# utility_hat.net
KiCad netlist of a schematic drawn in EAGLE
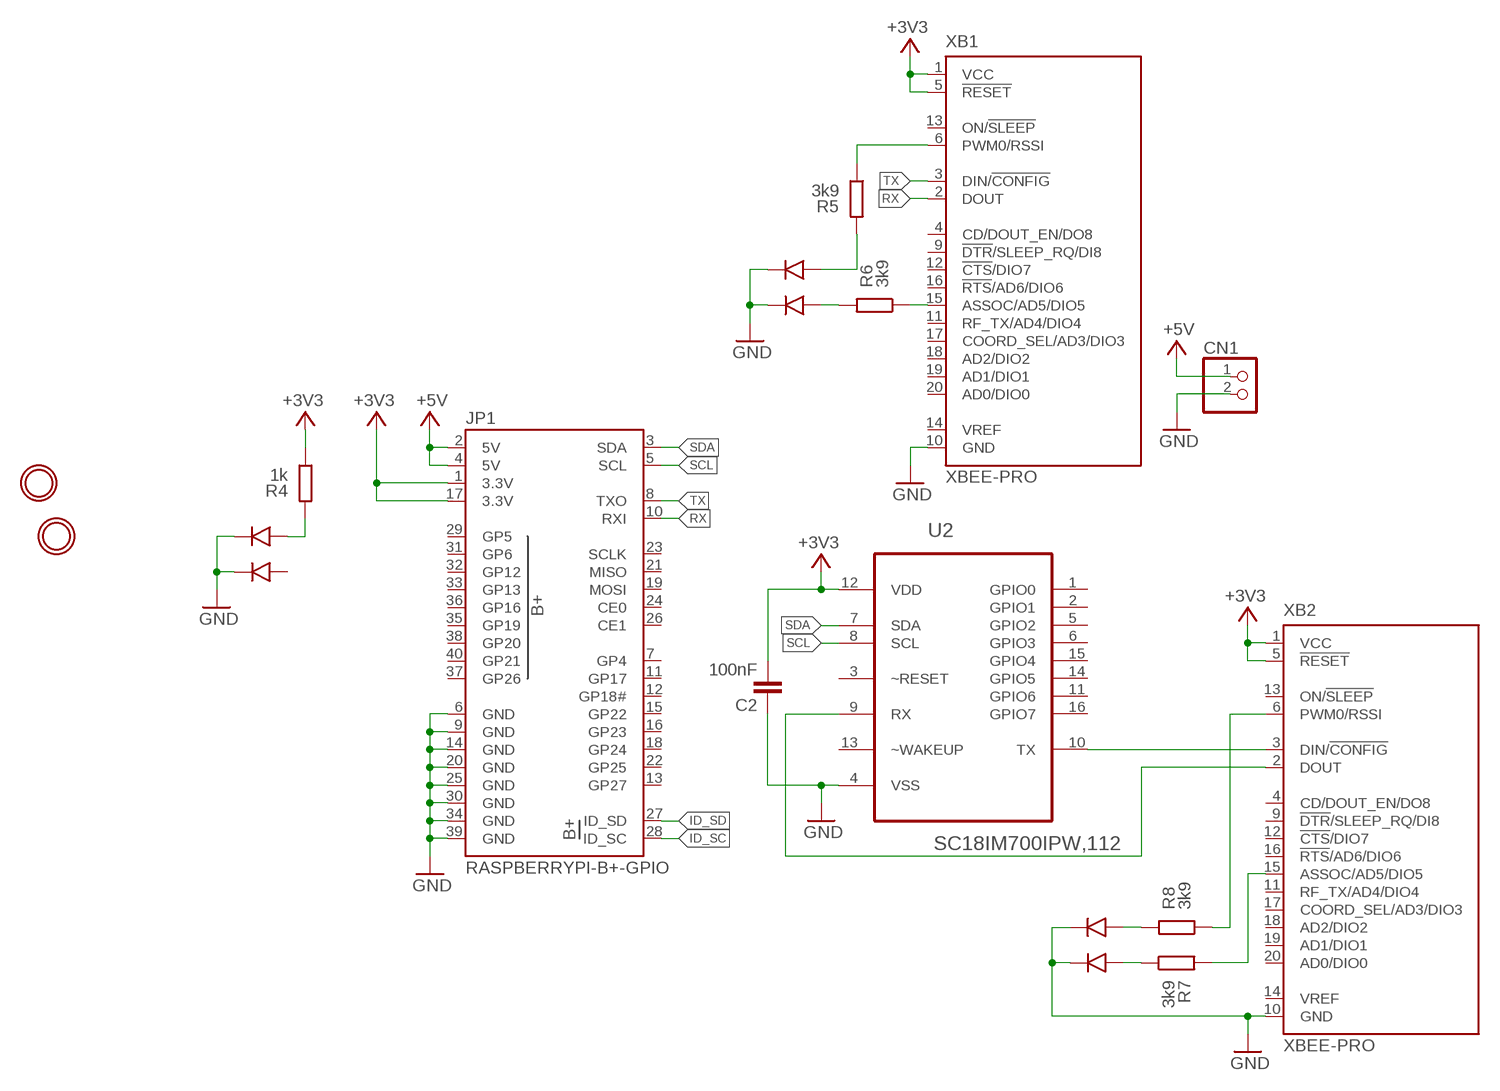
[diagram p0: schematic, sheet 1]

(export (version "E")
  (design (tool "Eeschema 10.0.6"))
  (components
    (comp (ref "C2")
      (value "100nF")
      (footprint "eagle-import:C0805K")
      (libsource (lib "eagle-import") (part "C-EUC0805K"))
    )
    (comp (ref "CN1")
      (value "JST_2PIN")
      (footprint "eagle-import:JSTPH2")
      (libsource (lib "eagle-import") (part "JST_2PIN"))
    )
    (comp (ref "JP1")
      (value "RASPBERRYPI-B+-GPIO")
      (footprint "eagle-import:2X20-SHROUDED")
      (libsource (lib "eagle-import") (part "RASPBERRYPI-B+-GPIO"))
    )
    (comp (ref "R4")
      (value "1k")
      (footprint "eagle-import:M0805")
      (fields (field (name "TOLERANCE") "5%"))
      (libsource (lib "eagle-import") (part "R-EU_M0805"))
    )
    (comp (ref "R5")
      (value "3k9")
      (footprint "eagle-import:M0805")
      (fields (field (name "TOLERANCE") "5%"))
      (libsource (lib "eagle-import") (part "R-EU_M0805"))
    )
    (comp (ref "R6")
      (value "3k9")
      (footprint "eagle-import:M0805")
      (fields (field (name "TOLERANCE") "5%"))
      (libsource (lib "eagle-import") (part "R-EU_M0805"))
    )
    (comp (ref "R7")
      (value "3k9")
      (footprint "eagle-import:M0805")
      (fields (field (name "TOLERANCE") "5%"))
      (libsource (lib "eagle-import") (part "R-EU_M0805"))
    )
    (comp (ref "R8")
      (value "3k9")
      (footprint "eagle-import:M0805")
      (fields (field (name "TOLERANCE") "5%"))
      (libsource (lib "eagle-import") (part "R-EU_M0805"))
    )
    (comp (ref "U$1")
      (value "BI-LEVEL-LED-INDICATOR")
      (footprint "eagle-import:BI-LEVEL-LED-INDICATOR")
      (libsource (lib "eagle-import") (part "BI-LEVEL-LED-INDICATOR"))
    )
    (comp (ref "U$2")
      (value "BI-LEVEL-LED-INDICATOR")
      (footprint "eagle-import:BI-LEVEL-LED-INDICATOR")
      (libsource (lib "eagle-import") (part "BI-LEVEL-LED-INDICATOR"))
    )
    (comp (ref "U$3")
      (value "BI-LEVEL-LED-INDICATOR")
      (footprint "eagle-import:BI-LEVEL-LED-INDICATOR")
      (libsource (lib "eagle-import") (part "BI-LEVEL-LED-INDICATOR"))
    )
    (comp (ref "U$4")
      (value "MOUNTINGHOLE3.0THIN")
      (footprint "eagle-import:MOUNTINGHOLE_3.0_PLATEDTHIN")
      (libsource (lib "eagle-import") (part "MOUNTINGHOLE3.0THIN"))
    )
    (comp (ref "U$5")
      (value "MOUNTINGHOLE3.0THIN")
      (footprint "eagle-import:MOUNTINGHOLE_3.0_PLATEDTHIN")
      (libsource (lib "eagle-import") (part "MOUNTINGHOLE3.0THIN"))
    )
    (comp (ref "U2")
      (value "SC18IM700IPW,112")
      (footprint "eagle-import:SOP65P640X110-16N")
      (libsource (lib "eagle-import") (part "SC18IM700IPW,112"))
    )
    (comp (ref "XB1")
      (value "XBEE-PRO")
      (footprint "eagle-import:XBEE-PRO")
      (fields (field (name "MPN") "XBP24-AWI-001"))
      (libsource (lib "eagle-import") (part "XBEE-PRO"))
    )
    (comp (ref "XB2")
      (value "XBEE-PRO")
      (footprint "eagle-import:XBEE-PRO")
      (fields
        (field (name "MPN") "XBP24-AWI-001")
        (field (name "MPN_1") "XBP24-AWI-001")
        (field (name "OC_FARNELL") "1337916")
        (field (name "OC_NEWARK") "42M2667")
      )
      (libsource (lib "eagle-import") (part "XBEE-PRO"))
    )
  )
  (nets
    (net (code "1") (name "+3V3") (class "Default")
      (node (ref "C2") (pin "2") (pinfunction "2_2") (pintype "passive"))
      (node (ref "JP1") (pin "1") (pinfunction "3.3V_1") (pintype "power_in"))
      (node (ref "JP1") (pin "17") (pinfunction "3.3V_17") (pintype "power_in"))
      (node (ref "R4") (pin "1") (pinfunction "1_1") (pintype "passive"))
      (node (ref "U2") (pin "12") (pinfunction "VDD_12") (pintype "power_in"))
      (node (ref "XB1") (pin "1") (pinfunction "VCC_1") (pintype "power_in"))
      (node (ref "XB1") (pin "5") (pinfunction "~{RESET}_5") (pintype "input"))
      (node (ref "XB2") (pin "1") (pinfunction "VCC_1") (pintype "power_in"))
      (node (ref "XB2") (pin "5") (pinfunction "~{RESET}_5") (pintype "input"))
    )
    (net (code "2") (name "+5V") (class "Default")
      (node (ref "CN1") (pin "1") (pinfunction "1_1") (pintype "passive"))
      (node (ref "JP1") (pin "2") (pinfunction "5V_2") (pintype "power_in"))
      (node (ref "JP1") (pin "4") (pinfunction "5V_4") (pintype "power_in"))
    )
    (net (code "3") (name "GND") (class "Default")
      (node (ref "C2") (pin "1") (pinfunction "1_1") (pintype "passive"))
      (node (ref "CN1") (pin "2") (pinfunction "2_2") (pintype "passive"))
      (node (ref "JP1") (pin "14") (pinfunction "GND_14") (pintype "power_in"))
      (node (ref "JP1") (pin "20") (pinfunction "GND_20") (pintype "power_in"))
      (node (ref "JP1") (pin "25") (pinfunction "GND_25") (pintype "power_in"))
      (node (ref "JP1") (pin "30") (pinfunction "GND_30") (pintype "power_in"))
      (node (ref "JP1") (pin "34") (pinfunction "GND_34") (pintype "power_in"))
      (node (ref "JP1") (pin "39") (pinfunction "GND_39") (pintype "power_in"))
      (node (ref "JP1") (pin "6") (pinfunction "GND_6") (pintype "power_in"))
      (node (ref "JP1") (pin "9") (pinfunction "GND_9") (pintype "power_in"))
      (node (ref "U$1") (pin "CATHODE1") (pinfunction "CATHODE1_CATHODE1") (pintype "bidirectional"))
      (node (ref "U$1") (pin "CATHODE2") (pinfunction "CATHODE2_CATHODE2") (pintype "bidirectional"))
      (node (ref "U$2") (pin "CATHODE1") (pinfunction "CATHODE1_CATHODE1") (pintype "bidirectional"))
      (node (ref "U$2") (pin "CATHODE2") (pinfunction "CATHODE2_CATHODE2") (pintype "bidirectional"))
      (node (ref "U$3") (pin "CATHODE1") (pinfunction "CATHODE1_CATHODE1") (pintype "bidirectional"))
      (node (ref "U$3") (pin "CATHODE2") (pinfunction "CATHODE2_CATHODE2") (pintype "bidirectional"))
      (node (ref "U2") (pin "4") (pinfunction "VSS_4") (pintype "passive"))
      (node (ref "XB1") (pin "10") (pinfunction "GND_10") (pintype "power_in"))
      (node (ref "XB2") (pin "10") (pinfunction "GND_10") (pintype "power_in"))
    )
    (net (code "4") (name "ID_SC") (class "Default")
      (node (ref "JP1") (pin "28") (pinfunction "ID_SC_28") (pintype "bidirectional"))
    )
    (net (code "5") (name "ID_SD") (class "Default")
      (node (ref "JP1") (pin "27") (pinfunction "ID_SD_27") (pintype "bidirectional"))
    )
    (net (code "6") (name "Net-(R4-Pad2)") (class "Default")
      (node (ref "R4") (pin "2") (pinfunction "2_2") (pintype "passive"))
      (node (ref "U$3") (pin "ANODE1") (pinfunction "ANODE1_ANODE1") (pintype "bidirectional"))
    )
    (net (code "7") (name "Net-(R5-Pad2)") (class "Default")
      (node (ref "R5") (pin "2") (pinfunction "2_2") (pintype "passive"))
      (node (ref "U$1") (pin "ANODE1") (pinfunction "ANODE1_ANODE1") (pintype "bidirectional"))
    )
    (net (code "8") (name "Net-(R6-Pad2)") (class "Default")
      (node (ref "R6") (pin "2") (pinfunction "2_2") (pintype "passive"))
      (node (ref "U$1") (pin "ANODE2") (pinfunction "ANODE2_ANODE2") (pintype "bidirectional"))
    )
    (net (code "9") (name "Net-(R7-Pad1)") (class "Default")
      (node (ref "R7") (pin "1") (pinfunction "1_1") (pintype "passive"))
      (node (ref "U$2") (pin "ANODE2") (pinfunction "ANODE2_ANODE2") (pintype "bidirectional"))
    )
    (net (code "10") (name "Net-(R8-Pad2)") (class "Default")
      (node (ref "R8") (pin "2") (pinfunction "2_2") (pintype "passive"))
      (node (ref "U$2") (pin "ANODE1") (pinfunction "ANODE1_ANODE1") (pintype "bidirectional"))
    )
    (net (code "11") (name "Net-(U2-RX)") (class "Default")
      (node (ref "U2") (pin "9") (pinfunction "RX_9") (pintype "input"))
      (node (ref "XB2") (pin "2") (pinfunction "DOUT_2") (pintype "output"))
    )
    (net (code "12") (name "Net-(U2-TX)") (class "Default")
      (node (ref "U2") (pin "10") (pinfunction "TX_10") (pintype "output"))
      (node (ref "XB2") (pin "3") (pinfunction "DIN/~{CONFIG}_3") (pintype "input"))
    )
    (net (code "13") (name "Net-(XB1-ASSOC{slash}AD5{slash}DIO5)") (class "Default")
      (node (ref "R6") (pin "1") (pinfunction "1_1") (pintype "passive"))
      (node (ref "XB1") (pin "15") (pinfunction "ASSOC/AD5/DIO5_15") (pintype "bidirectional"))
    )
    (net (code "14") (name "Net-(XB1-PWM0{slash}RSSI)") (class "Default")
      (node (ref "R5") (pin "1") (pinfunction "1_1") (pintype "passive"))
      (node (ref "XB1") (pin "6") (pinfunction "PWM0/RSSI_6") (pintype "output"))
    )
    (net (code "15") (name "Net-(XB2-ASSOC{slash}AD5{slash}DIO5)") (class "Default")
      (node (ref "R7") (pin "2") (pinfunction "2_2") (pintype "passive"))
      (node (ref "XB2") (pin "15") (pinfunction "ASSOC/AD5/DIO5_15") (pintype "bidirectional"))
    )
    (net (code "16") (name "Net-(XB2-PWM0{slash}RSSI)") (class "Default")
      (node (ref "R8") (pin "1") (pinfunction "1_1") (pintype "passive"))
      (node (ref "XB2") (pin "6") (pinfunction "PWM0/RSSI_6") (pintype "output"))
    )
    (net (code "17") (name "RX") (class "Default")
      (node (ref "JP1") (pin "10") (pinfunction "RXI_10") (pintype "input"))
      (node (ref "XB1") (pin "2") (pinfunction "DOUT_2") (pintype "output"))
    )
    (net (code "18") (name "SCL") (class "Default")
      (node (ref "JP1") (pin "5") (pinfunction "SCL_5") (pintype "bidirectional"))
      (node (ref "U2") (pin "8") (pinfunction "SCL_8") (pintype "input"))
    )
    (net (code "19") (name "SDA") (class "Default")
      (node (ref "JP1") (pin "3") (pinfunction "SDA_3") (pintype "bidirectional"))
      (node (ref "U2") (pin "7") (pinfunction "SDA_7") (pintype "bidirectional"))
    )
    (net (code "20") (name "TX") (class "Default")
      (node (ref "JP1") (pin "8") (pinfunction "TXO_8") (pintype "output"))
      (node (ref "XB1") (pin "3") (pinfunction "DIN/~{CONFIG}_3") (pintype "input"))
    )
    (net (code "21") (name "unconnected-(JP1-CE0-Pad24)") (class "Default")
      (node (ref "JP1") (pin "24") (pinfunction "CE0_24") (pintype "output"))
    )
    (net (code "22") (name "unconnected-(JP1-CE1-Pad26)") (class "Default")
      (node (ref "JP1") (pin "26") (pinfunction "CE1_26") (pintype "output"))
    )
    (net (code "23") (name "unconnected-(JP1-GP4-Pad7)") (class "Default")
      (node (ref "JP1") (pin "7") (pinfunction "GP4_7") (pintype "bidirectional"))
    )
    (net (code "24") (name "unconnected-(JP1-GP5-Pad29)") (class "Default")
      (node (ref "JP1") (pin "29") (pinfunction "GP5_29") (pintype "bidirectional"))
    )
    (net (code "25") (name "unconnected-(JP1-GP6-Pad31)") (class "Default")
      (node (ref "JP1") (pin "31") (pinfunction "GP6_31") (pintype "bidirectional"))
    )
    (net (code "26") (name "unconnected-(JP1-GP12-Pad32)") (class "Default")
      (node (ref "JP1") (pin "32") (pinfunction "GP12_32") (pintype "bidirectional"))
    )
    (net (code "27") (name "unconnected-(JP1-GP13-Pad33)") (class "Default")
      (node (ref "JP1") (pin "33") (pinfunction "GP13_33") (pintype "bidirectional"))
    )
    (net (code "28") (name "unconnected-(JP1-GP16-Pad36)") (class "Default")
      (node (ref "JP1") (pin "36") (pinfunction "GP16_36") (pintype "bidirectional"))
    )
    (net (code "29") (name "unconnected-(JP1-GP17-Pad11)") (class "Default")
      (node (ref "JP1") (pin "11") (pinfunction "GP17_11") (pintype "bidirectional"))
    )
    (net (code "30") (name "unconnected-(JP1-GP18#-Pad12)") (class "Default")
      (node (ref "JP1") (pin "12") (pinfunction "GP18#_12") (pintype "bidirectional"))
    )
    (net (code "31") (name "unconnected-(JP1-GP19-Pad35)") (class "Default")
      (node (ref "JP1") (pin "35") (pinfunction "GP19_35") (pintype "bidirectional"))
    )
    (net (code "32") (name "unconnected-(JP1-GP20-Pad38)") (class "Default")
      (node (ref "JP1") (pin "38") (pinfunction "GP20_38") (pintype "bidirectional"))
    )
    (net (code "33") (name "unconnected-(JP1-GP21-Pad40)") (class "Default")
      (node (ref "JP1") (pin "40") (pinfunction "GP21_40") (pintype "bidirectional"))
    )
    (net (code "34") (name "unconnected-(JP1-GP22-Pad15)") (class "Default")
      (node (ref "JP1") (pin "15") (pinfunction "GP22_15") (pintype "bidirectional"))
    )
    (net (code "35") (name "unconnected-(JP1-GP23-Pad16)") (class "Default")
      (node (ref "JP1") (pin "16") (pinfunction "GP23_16") (pintype "bidirectional"))
    )
    (net (code "36") (name "unconnected-(JP1-GP24-Pad18)") (class "Default")
      (node (ref "JP1") (pin "18") (pinfunction "GP24_18") (pintype "bidirectional"))
    )
    (net (code "37") (name "unconnected-(JP1-GP25-Pad22)") (class "Default")
      (node (ref "JP1") (pin "22") (pinfunction "GP25_22") (pintype "bidirectional"))
    )
    (net (code "38") (name "unconnected-(JP1-GP26-Pad37)") (class "Default")
      (node (ref "JP1") (pin "37") (pinfunction "GP26_37") (pintype "bidirectional"))
    )
    (net (code "39") (name "unconnected-(JP1-GP27-Pad13)") (class "Default")
      (node (ref "JP1") (pin "13") (pinfunction "GP27_13") (pintype "bidirectional"))
    )
    (net (code "40") (name "unconnected-(JP1-MISO-Pad21)") (class "Default")
      (node (ref "JP1") (pin "21") (pinfunction "MISO_21") (pintype "input"))
    )
    (net (code "41") (name "unconnected-(JP1-MOSI-Pad19)") (class "Default")
      (node (ref "JP1") (pin "19") (pinfunction "MOSI_19") (pintype "output"))
    )
    (net (code "42") (name "unconnected-(JP1-SCLK-Pad23)") (class "Default")
      (node (ref "JP1") (pin "23") (pinfunction "SCLK_23") (pintype "output"))
    )
    (net (code "43") (name "unconnected-(U$3-PadANODE2)") (class "Default")
      (node (ref "U$3") (pin "ANODE2") (pinfunction "ANODE2_ANODE2") (pintype "bidirectional"))
    )
    (net (code "44") (name "unconnected-(U2-GPIO0-Pad1)") (class "Default")
      (node (ref "U2") (pin "1") (pinfunction "GPIO0_1") (pintype "bidirectional"))
    )
    (net (code "45") (name "unconnected-(U2-GPIO1-Pad2)") (class "Default")
      (node (ref "U2") (pin "2") (pinfunction "GPIO1_2") (pintype "bidirectional"))
    )
    (net (code "46") (name "unconnected-(U2-GPIO2-Pad5)") (class "Default")
      (node (ref "U2") (pin "5") (pinfunction "GPIO2_5") (pintype "bidirectional"))
    )
    (net (code "47") (name "unconnected-(U2-GPIO3-Pad6)") (class "Default")
      (node (ref "U2") (pin "6") (pinfunction "GPIO3_6") (pintype "bidirectional"))
    )
    (net (code "48") (name "unconnected-(U2-GPIO4-Pad15)") (class "Default")
      (node (ref "U2") (pin "15") (pinfunction "GPIO4_15") (pintype "bidirectional"))
    )
    (net (code "49") (name "unconnected-(U2-GPIO5-Pad14)") (class "Default")
      (node (ref "U2") (pin "14") (pinfunction "GPIO5_14") (pintype "bidirectional"))
    )
    (net (code "50") (name "unconnected-(U2-GPIO6-Pad11)") (class "Default")
      (node (ref "U2") (pin "11") (pinfunction "GPIO6_11") (pintype "bidirectional"))
    )
    (net (code "51") (name "unconnected-(U2-GPIO7-Pad16)") (class "Default")
      (node (ref "U2") (pin "16") (pinfunction "GPIO7_16") (pintype "bidirectional"))
    )
    (net (code "52") (name "unconnected-(U2-~{RESET}-Pad3)") (class "Default")
      (node (ref "U2") (pin "3") (pinfunction "~{RESET}_3") (pintype "input"))
    )
    (net (code "53") (name "unconnected-(U2-~{WAKEUP}-Pad13)") (class "Default")
      (node (ref "U2") (pin "13") (pinfunction "~{WAKEUP}_13") (pintype "input"))
    )
    (net (code "54") (name "unconnected-(XB1-AD0{slash}DIO0-Pad20)") (class "Default")
      (node (ref "XB1") (pin "20") (pinfunction "AD0/DIO0_20") (pintype "bidirectional"))
    )
    (net (code "55") (name "unconnected-(XB1-AD1{slash}DIO1-Pad19)") (class "Default")
      (node (ref "XB1") (pin "19") (pinfunction "AD1/DIO1_19") (pintype "bidirectional"))
    )
    (net (code "56") (name "unconnected-(XB1-AD2{slash}DIO2-Pad18)") (class "Default")
      (node (ref "XB1") (pin "18") (pinfunction "AD2/DIO2_18") (pintype "bidirectional"))
    )
    (net (code "57") (name "unconnected-(XB1-CD{slash}DOUT_EN{slash}DO8-Pad4)") (class "Default")
      (node (ref "XB1") (pin "4") (pinfunction "CD/DOUT_EN/DO8_4") (pintype "output"))
    )
    (net (code "58") (name "unconnected-(XB1-COORD_SEL{slash}AD3{slash}DIO3-Pad17)") (class "Default")
      (node (ref "XB1") (pin "17") (pinfunction "COORD_SEL/AD3/DIO3_17") (pintype "bidirectional"))
    )
    (net (code "59") (name "unconnected-(XB1-ON{slash}~{SLEEP}-Pad13)") (class "Default")
      (node (ref "XB1") (pin "13") (pinfunction "ON/~{SLEEP}_13") (pintype "output"))
    )
    (net (code "60") (name "unconnected-(XB1-RF_TX{slash}AD4{slash}DIO4-Pad11)") (class "Default")
      (node (ref "XB1") (pin "11") (pinfunction "RF_TX/AD4/DIO4_11") (pintype "bidirectional"))
    )
    (net (code "61") (name "unconnected-(XB1-VREF-Pad14)") (class "Default")
      (node (ref "XB1") (pin "14") (pinfunction "VREF_14") (pintype "input"))
    )
    (net (code "62") (name "unconnected-(XB1-~{CTS}{slash}DIO7-Pad12)") (class "Default")
      (node (ref "XB1") (pin "12") (pinfunction "~{CTS}/DIO7_12") (pintype "bidirectional"))
    )
    (net (code "63") (name "unconnected-(XB1-~{DTR}{slash}SLEEP_RQ{slash}DI8-Pad9)") (class "Default")
      (node (ref "XB1") (pin "9") (pinfunction "~{DTR}/SLEEP_RQ/DI8_9") (pintype "bidirectional"))
    )
    (net (code "64") (name "unconnected-(XB1-~{RTS}{slash}AD6{slash}DIO6-Pad16)") (class "Default")
      (node (ref "XB1") (pin "16") (pinfunction "~{RTS}/AD6/DIO6_16") (pintype "bidirectional"))
    )
    (net (code "65") (name "unconnected-(XB2-AD0{slash}DIO0-Pad20)") (class "Default")
      (node (ref "XB2") (pin "20") (pinfunction "AD0/DIO0_20") (pintype "bidirectional"))
    )
    (net (code "66") (name "unconnected-(XB2-AD1{slash}DIO1-Pad19)") (class "Default")
      (node (ref "XB2") (pin "19") (pinfunction "AD1/DIO1_19") (pintype "bidirectional"))
    )
    (net (code "67") (name "unconnected-(XB2-AD2{slash}DIO2-Pad18)") (class "Default")
      (node (ref "XB2") (pin "18") (pinfunction "AD2/DIO2_18") (pintype "bidirectional"))
    )
    (net (code "68") (name "unconnected-(XB2-CD{slash}DOUT_EN{slash}DO8-Pad4)") (class "Default")
      (node (ref "XB2") (pin "4") (pinfunction "CD/DOUT_EN/DO8_4") (pintype "output"))
    )
    (net (code "69") (name "unconnected-(XB2-COORD_SEL{slash}AD3{slash}DIO3-Pad17)") (class "Default")
      (node (ref "XB2") (pin "17") (pinfunction "COORD_SEL/AD3/DIO3_17") (pintype "bidirectional"))
    )
    (net (code "70") (name "unconnected-(XB2-ON{slash}~{SLEEP}-Pad13)") (class "Default")
      (node (ref "XB2") (pin "13") (pinfunction "ON/~{SLEEP}_13") (pintype "output"))
    )
    (net (code "71") (name "unconnected-(XB2-RF_TX{slash}AD4{slash}DIO4-Pad11)") (class "Default")
      (node (ref "XB2") (pin "11") (pinfunction "RF_TX/AD4/DIO4_11") (pintype "bidirectional"))
    )
    (net (code "72") (name "unconnected-(XB2-VREF-Pad14)") (class "Default")
      (node (ref "XB2") (pin "14") (pinfunction "VREF_14") (pintype "input"))
    )
    (net (code "73") (name "unconnected-(XB2-~{CTS}{slash}DIO7-Pad12)") (class "Default")
      (node (ref "XB2") (pin "12") (pinfunction "~{CTS}/DIO7_12") (pintype "bidirectional"))
    )
    (net (code "74") (name "unconnected-(XB2-~{DTR}{slash}SLEEP_RQ{slash}DI8-Pad9)") (class "Default")
      (node (ref "XB2") (pin "9") (pinfunction "~{DTR}/SLEEP_RQ/DI8_9") (pintype "bidirectional"))
    )
    (net (code "75") (name "unconnected-(XB2-~{RTS}{slash}AD6{slash}DIO6-Pad16)") (class "Default")
      (node (ref "XB2") (pin "16") (pinfunction "~{RTS}/AD6/DIO6_16") (pintype "bidirectional"))
    )
  )
)
